# VCC33.net
KiCad netlist of a schematic drawn in Altium Designer
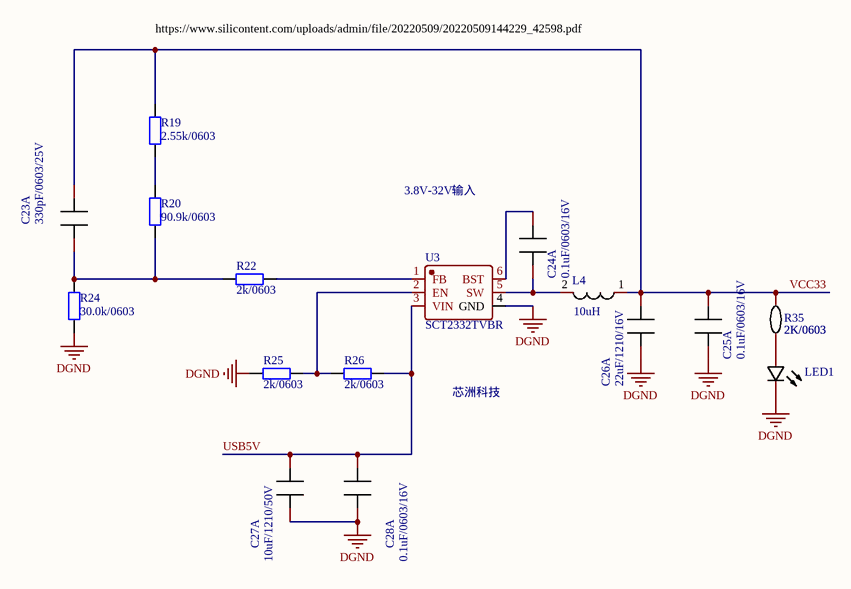
[diagram p0: VCC33.SchDoc]

(export (version "E")
  (design (tool "Eeschema 10.0.6"))
  (components
    (comp (ref "C23")
      (value "330pF/0603/25V")
      (footprint "CAP0603")
      (description "SURFACE MOUNT CAPACITOR 0.031 X 0.061 INCHES")
      (libsource (lib "altium-import") (part "root_0_CAP0603_"))
    )
    (comp (ref "C24")
      (value "0.1uF/0603/16V")
      (footprint "CAP0603")
      (description "SURFACE MOUNT CAPACITOR 0.031 X 0.061 INCHES")
      (libsource (lib "altium-import") (part "root_0_CAP0603_"))
    )
    (comp (ref "C25")
      (value "0.1uF/0603/16V")
      (footprint "CAP0603")
      (description "SURFACE MOUNT CAPACITOR 0.031 X 0.061 INCHES")
      (libsource (lib "altium-import") (part "root_0_CAP0603_"))
    )
    (comp (ref "C26")
      (value "22uF/1210/16V")
      (footprint "CAP1210-CAPC3225X140N")
      (description "SURFACE MOUNT CAPACITOR 0.031 X 0.061 INCHES")
      (libsource (lib "altium-import") (part "root_0_CAP0603_"))
    )
    (comp (ref "C27")
      (value "10uF/1210/50V")
      (footprint "CAP1210-CAPC3225X140N")
      (description "SURFACE MOUNT CAPACITOR 0.031 X 0.061 INCHES")
      (libsource (lib "altium-import") (part "root_0_CAP0603_"))
    )
    (comp (ref "C28")
      (value "0.1uF/0603/16V")
      (footprint "CAP0603")
      (description "SURFACE MOUNT CAPACITOR 0.031 X 0.061 INCHES")
      (libsource (lib "altium-import") (part "root_0_CAP0603_"))
    )
    (comp (ref "L4")
      (value "10uH")
      (footprint "IND-SMD_L4.7-W4.7-6.5uH")
      (libsource (lib "altium-import") (part "root_2_IND-MOLDED_"))
    )
    (comp (ref "LED1")
      (value "19-217/GHC-YR1S2/3T")
      (footprint "LED_0603_KA")
      (fields (field (name "MANUFACTURER") "EVERLIGHT"))
      (libsource (lib "altium-import") (part "root_3_19-217/GHC-YR1S2/3T_"))
    )
    (comp (ref "R19")
      (value "2.55k/0603")
      (footprint "RES0603")
      (description "Resistor")
      (fields (field (name "PUBLISHER") "Altium Limited"))
      (libsource (lib "") (part "Res2_1"))
    )
    (comp (ref "R20")
      (value "90.9k/0603")
      (footprint "RES0603")
      (description "Resistor")
      (fields (field (name "PUBLISHER") "Altium Limited"))
      (libsource (lib "") (part "Res2_1"))
    )
    (comp (ref "R22")
      (value "2k/0603")
      (footprint "RES0603")
      (description "Resistor")
      (fields (field (name "PUBLISHER") "Altium Limited"))
      (libsource (lib "Miscellaneous Devices") (part "Res2"))
    )
    (comp (ref "R24")
      (value "30.0k/0603")
      (footprint "RES0603")
      (description "Resistor")
      (fields (field (name "PUBLISHER") "Altium Limited"))
      (libsource (lib "") (part "Res2_1"))
    )
    (comp (ref "R25")
      (value "2k/0603")
      (footprint "RES0603")
      (description "Resistor")
      (fields (field (name "PUBLISHER") "Altium Limited"))
      (libsource (lib "Miscellaneous Devices") (part "Res2"))
    )
    (comp (ref "R26")
      (value "2k/0603")
      (footprint "RES0603")
      (description "Resistor")
      (fields (field (name "PUBLISHER") "Altium Limited"))
      (libsource (lib "Miscellaneous Devices") (part "Res2"))
    )
    (comp (ref "R35")
      (value "2K/0603")
      (footprint "RES0603")
      (fields
        (field (name "NAME") "2K/0603")
        (field (name "MANUFACTURER") "UniOhm")
        (field (name "MANUFACTURER PART") "0402WGF2201TCE")
      )
      (libsource (lib "altium-import") (part "root_3_2.2K_"))
    )
    (comp (ref "U3")
      (value "SCT2332TVBR")
      (footprint "SCT2332TVBR-TSOT23-6")
      (description "3.8V-32V Vin, 3A Synchronous Step-down DCDC Converter")
      (libsource (lib "ChargingPile") (part "SCT2332TVBR"))
    )
  )
  (nets
    (net (code "1") (name "/USB5V") (class "Default")
      (node (ref "C27") (pin "1") (pintype "passive"))
      (node (ref "C28") (pin "1") (pintype "passive"))
      (node (ref "R26") (pin "1") (pinfunction "1_1") (pintype "passive"))
      (node (ref "U3") (pin "3") (pinfunction "VIN_3") (pintype "passive"))
    )
    (net (code "2") (name "/VCC33") (class "Default")
      (node (ref "C23") (pin "1") (pintype "passive"))
      (node (ref "C25") (pin "1") (pintype "passive"))
      (node (ref "C26") (pin "1") (pintype "passive"))
      (node (ref "L4") (pin "1") (pintype "passive"))
      (node (ref "R19") (pin "2") (pinfunction "2_2") (pintype "passive"))
      (node (ref "R35") (pin "1") (pinfunction "1_1") (pintype "passive"))
    )
    (net (code "3") (name "DGND") (class "Default")
      (node (ref "C25") (pin "2") (pintype "passive"))
      (node (ref "C26") (pin "2") (pintype "passive"))
      (node (ref "C27") (pin "2") (pintype "passive"))
      (node (ref "C28") (pin "2") (pintype "passive"))
      (node (ref "LED1") (pin "2") (pinfunction "C_2") (pintype "passive"))
      (node (ref "R24") (pin "1") (pinfunction "1_1") (pintype "passive"))
      (node (ref "R25") (pin "2") (pinfunction "2_2") (pintype "passive"))
      (node (ref "U3") (pin "4") (pinfunction "GND_4") (pintype "passive"))
    )
    (net (code "4") (name "Net-(C23-Pad2)") (class "Default")
      (node (ref "C23") (pin "2") (pintype "passive"))
      (node (ref "R20") (pin "1") (pinfunction "1_1") (pintype "passive"))
      (node (ref "R22") (pin "2") (pinfunction "2_2") (pintype "passive"))
      (node (ref "R24") (pin "2") (pinfunction "2_2") (pintype "passive"))
    )
    (net (code "5") (name "Net-(LED1-A)") (class "Default")
      (node (ref "LED1") (pin "1") (pinfunction "A_1") (pintype "passive"))
      (node (ref "R35") (pin "2") (pinfunction "2_2") (pintype "passive"))
    )
    (net (code "6") (name "Net-(R19-Pad1)") (class "Default")
      (node (ref "R19") (pin "1") (pinfunction "1_1") (pintype "passive"))
      (node (ref "R20") (pin "2") (pinfunction "2_2") (pintype "passive"))
    )
    (net (code "7") (name "Net-(U3-BST)") (class "Default")
      (node (ref "C24") (pin "1") (pintype "passive"))
      (node (ref "U3") (pin "6") (pinfunction "BST_6") (pintype "passive"))
    )
    (net (code "8") (name "Net-(U3-EN)") (class "Default")
      (node (ref "R25") (pin "1") (pinfunction "1_1") (pintype "passive"))
      (node (ref "R26") (pin "2") (pinfunction "2_2") (pintype "passive"))
      (node (ref "U3") (pin "2") (pinfunction "EN_2") (pintype "passive"))
    )
    (net (code "9") (name "Net-(U3-FB)") (class "Default")
      (node (ref "R22") (pin "1") (pinfunction "1_1") (pintype "passive"))
      (node (ref "U3") (pin "1") (pinfunction "FB_1") (pintype "passive"))
    )
    (net (code "10") (name "Net-(U3-SW)") (class "Default")
      (node (ref "C24") (pin "2") (pintype "passive"))
      (node (ref "L4") (pin "2") (pintype "passive"))
      (node (ref "U3") (pin "5") (pinfunction "SW_5") (pintype "passive"))
    )
  )
)
